# Arduino_Uno_Data_Logger_with_DHT.net
KiCad netlist of a schematic drawn in EAGLE
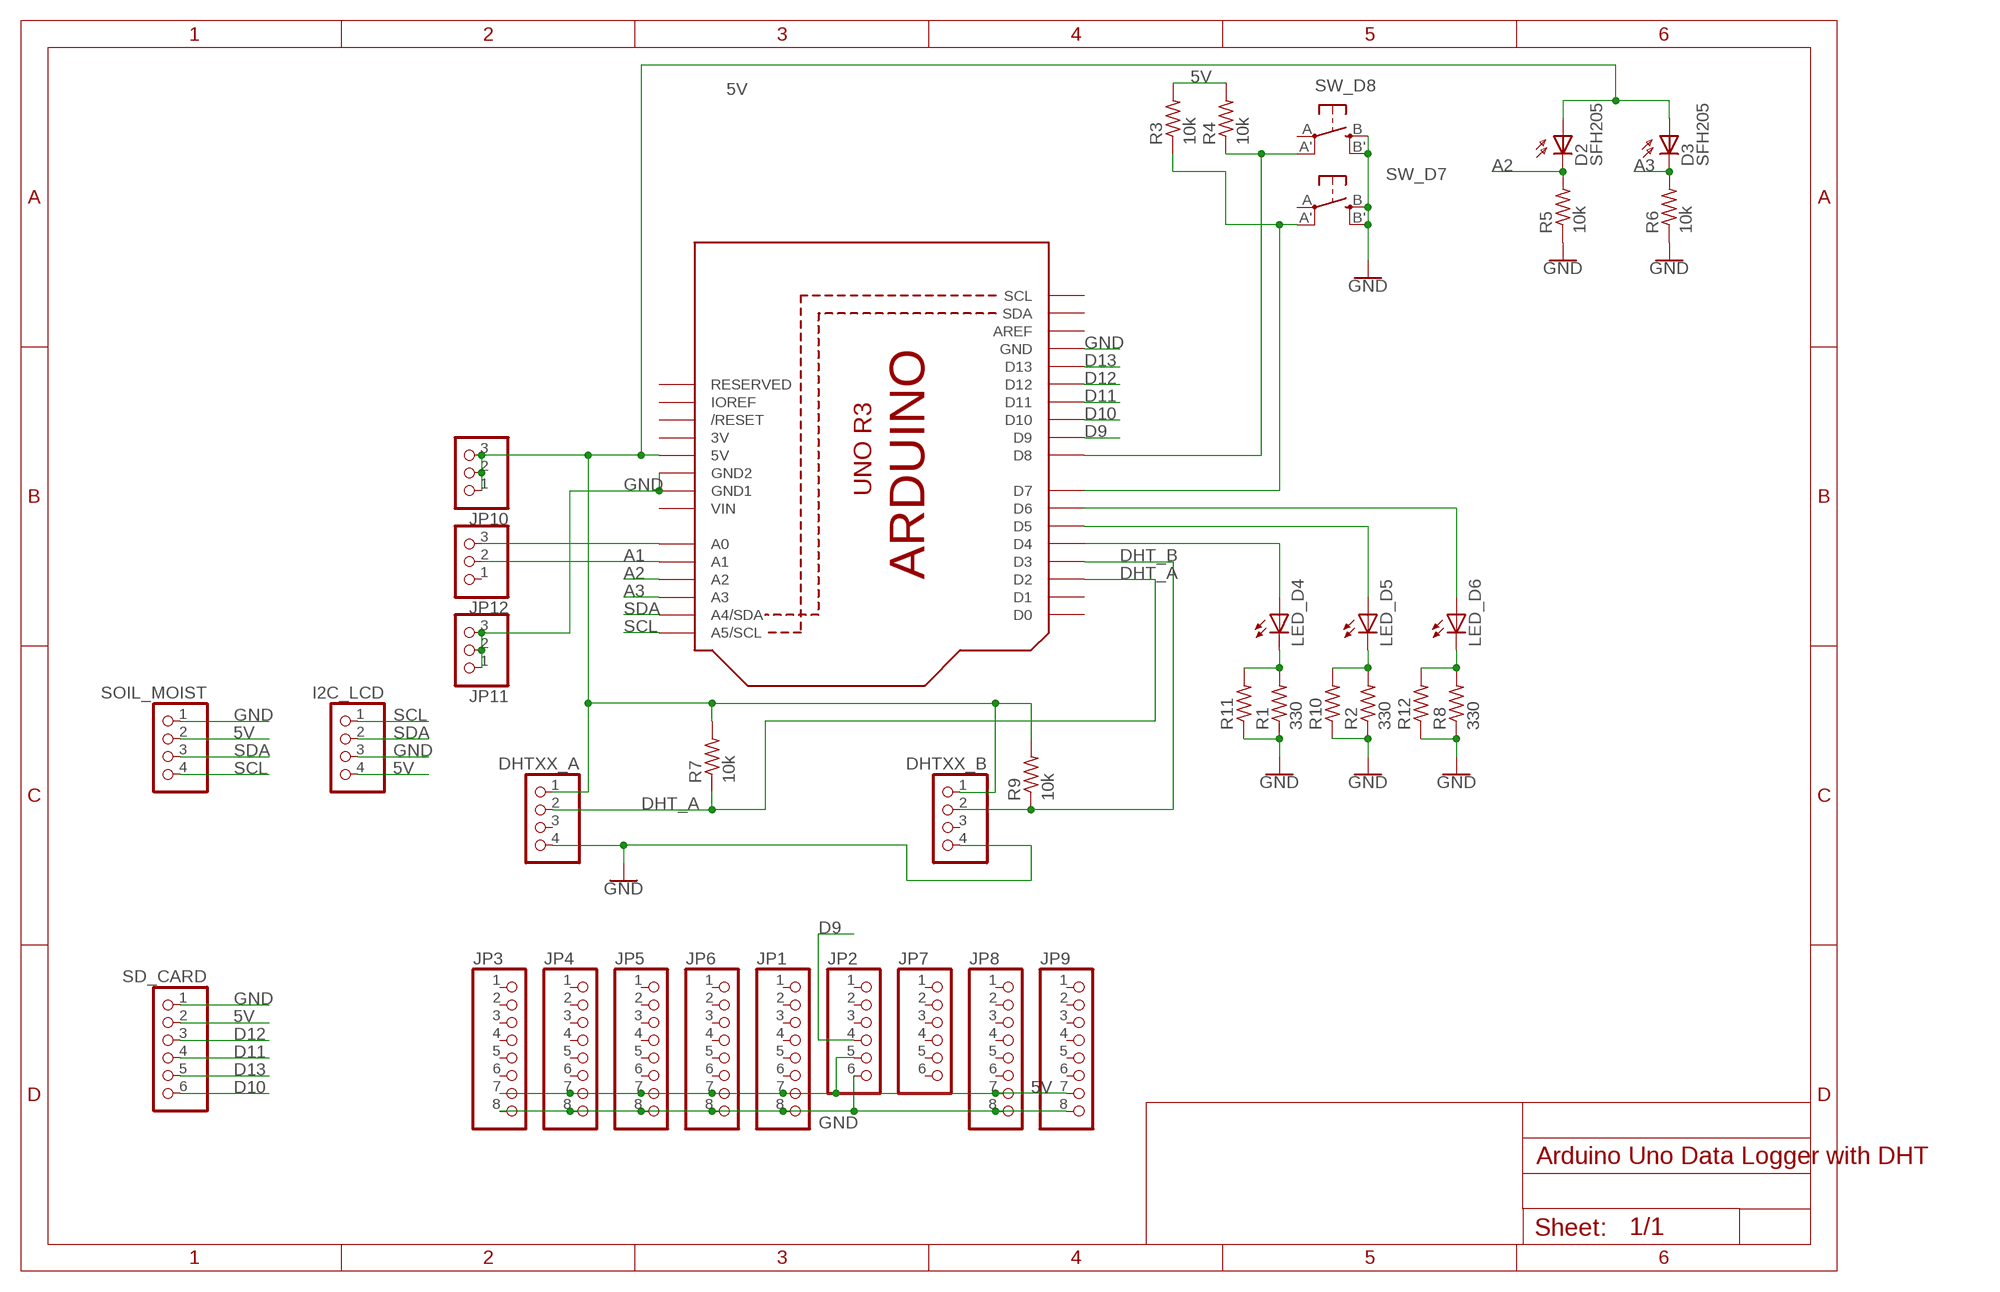
[diagram p0: schematic, sheet 1]

(export (version "E")
  (design (tool "Eeschema 10.0.6"))
  (components
    (comp (ref "D2")
      (value "SFH205")
      (footprint "eagle-import:SFH205")
      (libsource (lib "eagle-import") (part "SFH205"))
    )
    (comp (ref "D3")
      (value "SFH205")
      (footprint "eagle-import:SFH205")
      (libsource (lib "eagle-import") (part "SFH205"))
    )
    (comp (ref "DHTXX_A")
      (value "PINHD-1X4")
      (footprint "eagle-import:1X04")
      (libsource (lib "eagle-import") (part "PINHD-1X4"))
    )
    (comp (ref "DHTXX_B")
      (value "PINHD-1X4")
      (footprint "eagle-import:1X04")
      (libsource (lib "eagle-import") (part "PINHD-1X4"))
    )
    (comp (ref "I2C_LCD")
      (value "PINHD-1X4")
      (footprint "eagle-import:1X04")
      (libsource (lib "eagle-import") (part "PINHD-1X4"))
    )
    (comp (ref "JP1")
      (value "PINHD-1X8CLEANBIG")
      (footprint "eagle-import:1X08-CLEANBIG")
      (libsource (lib "eagle-import") (part "PINHD-1X8CLEANBIG"))
    )
    (comp (ref "JP2")
      (value "PINHD-1X6CB")
      (footprint "eagle-import:1X06-CLEANBIG")
      (libsource (lib "eagle-import") (part "PINHD-1X6CB"))
    )
    (comp (ref "JP3")
      (value "PINHD-1X8CLEANBIG")
      (footprint "eagle-import:1X08-CLEANBIG")
      (libsource (lib "eagle-import") (part "PINHD-1X8CLEANBIG"))
    )
    (comp (ref "JP4")
      (value "PINHD-1X8CLEANBIG")
      (footprint "eagle-import:1X08-CLEANBIG")
      (libsource (lib "eagle-import") (part "PINHD-1X8CLEANBIG"))
    )
    (comp (ref "JP5")
      (value "PINHD-1X8CLEANBIG")
      (footprint "eagle-import:1X08-CLEANBIG")
      (libsource (lib "eagle-import") (part "PINHD-1X8CLEANBIG"))
    )
    (comp (ref "JP6")
      (value "PINHD-1X8CLEANBIG")
      (footprint "eagle-import:1X08-CLEANBIG")
      (libsource (lib "eagle-import") (part "PINHD-1X8CLEANBIG"))
    )
    (comp (ref "JP7")
      (value "PINHD-1X6CB")
      (footprint "eagle-import:1X06-CLEANBIG")
      (libsource (lib "eagle-import") (part "PINHD-1X6CB"))
    )
    (comp (ref "JP8")
      (value "PINHD-1X8CLEANBIG")
      (footprint "eagle-import:1X08-CLEANBIG")
      (libsource (lib "eagle-import") (part "PINHD-1X8CLEANBIG"))
    )
    (comp (ref "JP9")
      (value "PINHD-1X8CLEANBIG")
      (footprint "eagle-import:1X08-CLEANBIG")
      (libsource (lib "eagle-import") (part "PINHD-1X8CLEANBIG"))
    )
    (comp (ref "JP10")
      (value "PINHD-1X3CB")
      (footprint "eagle-import:1X03-CLEANBIG")
      (libsource (lib "eagle-import") (part "PINHD-1X3CB"))
    )
    (comp (ref "JP11")
      (value "PINHD-1X3CB")
      (footprint "eagle-import:1X03-CLEANBIG")
      (libsource (lib "eagle-import") (part "PINHD-1X3CB"))
    )
    (comp (ref "JP12")
      (value "PINHD-1X3CB")
      (footprint "eagle-import:1X03-CLEANBIG")
      (libsource (lib "eagle-import") (part "PINHD-1X3CB"))
    )
    (comp (ref "LED_D4")
      (value "LED5MM")
      (footprint "eagle-import:LED5MM")
      (libsource (lib "eagle-import") (part "LED5MM"))
    )
    (comp (ref "LED_D5")
      (value "LED5MM")
      (footprint "eagle-import:LED5MM")
      (libsource (lib "eagle-import") (part "LED5MM"))
    )
    (comp (ref "LED_D6")
      (value "LED5MM")
      (footprint "eagle-import:LED5MM")
      (libsource (lib "eagle-import") (part "LED5MM"))
    )
    (comp (ref "R1")
      (value "330")
      (footprint "eagle-import:0207_10")
      (libsource (lib "eagle-import") (part "R-US_0207/10"))
    )
    (comp (ref "R2")
      (value "330")
      (footprint "eagle-import:0207_10")
      (libsource (lib "eagle-import") (part "R-US_0207/10"))
    )
    (comp (ref "R3")
      (value "10k")
      (footprint "eagle-import:0207_10")
      (libsource (lib "eagle-import") (part "R-US_0207/10"))
    )
    (comp (ref "R4")
      (value "10k")
      (footprint "eagle-import:0207_10")
      (libsource (lib "eagle-import") (part "R-US_0207/10"))
    )
    (comp (ref "R5")
      (value "10k")
      (footprint "eagle-import:0207_10")
      (libsource (lib "eagle-import") (part "R-US_0207/10"))
    )
    (comp (ref "R6")
      (value "10k")
      (footprint "eagle-import:0207_10")
      (libsource (lib "eagle-import") (part "R-US_0207/10"))
    )
    (comp (ref "R7")
      (value "10k")
      (footprint "eagle-import:0207_10")
      (libsource (lib "eagle-import") (part "R-US_0207/10"))
    )
    (comp (ref "R8")
      (value "330")
      (footprint "eagle-import:0207_10")
      (libsource (lib "eagle-import") (part "R-US_0207/10"))
    )
    (comp (ref "R9")
      (value "10k")
      (footprint "eagle-import:0207_10")
      (libsource (lib "eagle-import") (part "R-US_0207/10"))
    )
    (comp (ref "R10")
      (value "R-US_R2010")
      (footprint "eagle-import:R2010")
      (libsource (lib "eagle-import") (part "R-US_R2010"))
    )
    (comp (ref "R11")
      (value "R-US_R2010")
      (footprint "eagle-import:R2010")
      (libsource (lib "eagle-import") (part "R-US_R2010"))
    )
    (comp (ref "R12")
      (value "R-US_R2010")
      (footprint "eagle-import:R2010")
      (libsource (lib "eagle-import") (part "R-US_R2010"))
    )
    (comp (ref "SD_CARD")
      (value "PINHD-1X6")
      (footprint "eagle-import:1X06")
      (libsource (lib "eagle-import") (part "pinhead_PINHD-1X6"))
    )
    (comp (ref "SOIL_MOIST")
      (value "PINHD-1X4")
      (footprint "eagle-import:1X04")
      (libsource (lib "eagle-import") (part "PINHD-1X4"))
    )
    (comp (ref "SW_D7")
      (value "SPST_TACT-EVQQ2")
      (footprint "eagle-import:EVQ-Q2")
      (libsource (lib "eagle-import") (part "SPST_TACT-EVQQ2"))
    )
    (comp (ref "SW_D8")
      (value "SPST_TACT-EVQQ2")
      (footprint "eagle-import:EVQ-Q2")
      (libsource (lib "eagle-import") (part "SPST_TACT-EVQQ2"))
    )
    (comp (ref "U1")
      (value "ARDUINOR3-DIMENSION")
      (footprint "eagle-import:ARDUINOR3")
      (libsource (lib "eagle-import") (part "ARDUINOR3-DIMENSION"))
    )
  )
  (nets
    (net (code "1") (name "/3V") (class "Default")
      (node (ref "U1") (pin "3V") (pinfunction "3V_3V") (pintype "power_in"))
    )
    (net (code "2") (name "/5V") (class "Default")
      (node (ref "D2") (pin "A") (pinfunction "A_A") (pintype "passive"))
      (node (ref "D3") (pin "A") (pinfunction "A_A") (pintype "passive"))
      (node (ref "DHTXX_A") (pin "1") (pinfunction "1_1") (pintype "passive"))
      (node (ref "DHTXX_B") (pin "1") (pinfunction "1_1") (pintype "passive"))
      (node (ref "I2C_LCD") (pin "4") (pinfunction "4_4") (pintype "passive"))
      (node (ref "JP1") (pin "7") (pinfunction "7_7") (pintype "passive"))
      (node (ref "JP10") (pin "1") (pinfunction "1_1") (pintype "passive"))
      (node (ref "JP10") (pin "2") (pinfunction "2_2") (pintype "passive"))
      (node (ref "JP10") (pin "3") (pinfunction "3_3") (pintype "passive"))
      (node (ref "JP2") (pin "5") (pinfunction "5_5") (pintype "passive"))
      (node (ref "JP3") (pin "7") (pinfunction "7_7") (pintype "passive"))
      (node (ref "JP4") (pin "7") (pinfunction "7_7") (pintype "passive"))
      (node (ref "JP5") (pin "7") (pinfunction "7_7") (pintype "passive"))
      (node (ref "JP6") (pin "7") (pinfunction "7_7") (pintype "passive"))
      (node (ref "JP8") (pin "7") (pinfunction "7_7") (pintype "passive"))
      (node (ref "JP9") (pin "7") (pinfunction "7_7") (pintype "passive"))
      (node (ref "R3") (pin "2") (pinfunction "2_2") (pintype "passive"))
      (node (ref "R4") (pin "2") (pinfunction "2_2") (pintype "passive"))
      (node (ref "R7") (pin "2") (pinfunction "2_2") (pintype "passive"))
      (node (ref "R9") (pin "2") (pinfunction "2_2") (pintype "passive"))
      (node (ref "SD_CARD") (pin "2") (pinfunction "2_2") (pintype "passive"))
      (node (ref "SOIL_MOIST") (pin "2") (pinfunction "2_2") (pintype "passive"))
      (node (ref "U1") (pin "5V") (pinfunction "5V_5V") (pintype "power_in"))
    )
    (net (code "3") (name "/A1") (class "Default")
      (node (ref "JP12") (pin "2") (pinfunction "2_2") (pintype "passive"))
      (node (ref "U1") (pin "A1") (pinfunction "A1_A1") (pintype "bidirectional"))
    )
    (net (code "4") (name "/A2") (class "Default")
      (node (ref "D2") (pin "K") (pinfunction "C_K") (pintype "passive"))
      (node (ref "R5") (pin "2") (pinfunction "2_2") (pintype "passive"))
      (node (ref "U1") (pin "A2") (pinfunction "A2_A2") (pintype "bidirectional"))
    )
    (net (code "5") (name "/A3") (class "Default")
      (node (ref "D3") (pin "K") (pinfunction "C_K") (pintype "passive"))
      (node (ref "R6") (pin "2") (pinfunction "2_2") (pintype "passive"))
      (node (ref "U1") (pin "A3") (pinfunction "A3_A3") (pintype "bidirectional"))
    )
    (net (code "6") (name "/D9") (class "Default")
      (node (ref "JP2") (pin "4") (pinfunction "4_4") (pintype "passive"))
      (node (ref "U1") (pin "D9") (pinfunction "D9_D9") (pintype "bidirectional"))
    )
    (net (code "7") (name "/D10") (class "Default")
      (node (ref "SD_CARD") (pin "6") (pinfunction "6_6") (pintype "passive"))
      (node (ref "U1") (pin "D10") (pinfunction "D10_D10") (pintype "bidirectional"))
    )
    (net (code "8") (name "/D11") (class "Default")
      (node (ref "SD_CARD") (pin "4") (pinfunction "4_4") (pintype "passive"))
      (node (ref "U1") (pin "D11") (pinfunction "D11_D11") (pintype "bidirectional"))
    )
    (net (code "9") (name "/D12") (class "Default")
      (node (ref "SD_CARD") (pin "3") (pinfunction "3_3") (pintype "passive"))
      (node (ref "U1") (pin "D12") (pinfunction "D12_D12") (pintype "bidirectional"))
    )
    (net (code "10") (name "/D13") (class "Default")
      (node (ref "SD_CARD") (pin "5") (pinfunction "5_5") (pintype "passive"))
      (node (ref "U1") (pin "D13") (pinfunction "D13_D13") (pintype "bidirectional"))
    )
    (net (code "11") (name "/DHT_A") (class "Default")
      (node (ref "DHTXX_A") (pin "2") (pinfunction "2_2") (pintype "passive"))
      (node (ref "R7") (pin "1") (pinfunction "1_1") (pintype "passive"))
      (node (ref "U1") (pin "D2") (pinfunction "D2_D2") (pintype "bidirectional"))
    )
    (net (code "12") (name "/DHT_B") (class "Default")
      (node (ref "DHTXX_B") (pin "2") (pinfunction "2_2") (pintype "passive"))
      (node (ref "R9") (pin "1") (pinfunction "1_1") (pintype "passive"))
      (node (ref "U1") (pin "D3") (pinfunction "D3_D3") (pintype "bidirectional"))
    )
    (net (code "13") (name "/SCL") (class "Default")
      (node (ref "I2C_LCD") (pin "1") (pinfunction "1_1") (pintype "passive"))
      (node (ref "SOIL_MOIST") (pin "4") (pinfunction "4_4") (pintype "passive"))
      (node (ref "U1") (pin "A5") (pinfunction "A5/SCL_A5") (pintype "bidirectional"))
    )
    (net (code "14") (name "/SDA") (class "Default")
      (node (ref "I2C_LCD") (pin "2") (pinfunction "2_2") (pintype "passive"))
      (node (ref "SOIL_MOIST") (pin "3") (pinfunction "3_3") (pintype "passive"))
      (node (ref "U1") (pin "A4") (pinfunction "A4/SDA_A4") (pintype "bidirectional"))
    )
    (net (code "15") (name "/VIN") (class "Default")
      (node (ref "U1") (pin "VIN") (pinfunction "VIN_VIN") (pintype "power_in"))
    )
    (net (code "16") (name "GND") (class "Default")
      (node (ref "DHTXX_A") (pin "4") (pinfunction "4_4") (pintype "passive"))
      (node (ref "DHTXX_B") (pin "4") (pinfunction "4_4") (pintype "passive"))
      (node (ref "I2C_LCD") (pin "3") (pinfunction "3_3") (pintype "passive"))
      (node (ref "JP1") (pin "8") (pinfunction "8_8") (pintype "passive"))
      (node (ref "JP11") (pin "1") (pinfunction "1_1") (pintype "passive"))
      (node (ref "JP11") (pin "2") (pinfunction "2_2") (pintype "passive"))
      (node (ref "JP11") (pin "3") (pinfunction "3_3") (pintype "passive"))
      (node (ref "JP2") (pin "6") (pinfunction "6_6") (pintype "passive"))
      (node (ref "JP3") (pin "8") (pinfunction "8_8") (pintype "passive"))
      (node (ref "JP4") (pin "8") (pinfunction "8_8") (pintype "passive"))
      (node (ref "JP5") (pin "8") (pinfunction "8_8") (pintype "passive"))
      (node (ref "JP6") (pin "8") (pinfunction "8_8") (pintype "passive"))
      (node (ref "JP8") (pin "8") (pinfunction "8_8") (pintype "passive"))
      (node (ref "JP9") (pin "8") (pinfunction "8_8") (pintype "passive"))
      (node (ref "R1") (pin "1") (pinfunction "1_1") (pintype "passive"))
      (node (ref "R10") (pin "1") (pinfunction "1_1") (pintype "passive"))
      (node (ref "R11") (pin "1") (pinfunction "1_1") (pintype "passive"))
      (node (ref "R12") (pin "1") (pinfunction "1_1") (pintype "passive"))
      (node (ref "R2") (pin "1") (pinfunction "1_1") (pintype "passive"))
      (node (ref "R5") (pin "1") (pinfunction "1_1") (pintype "passive"))
      (node (ref "R6") (pin "1") (pinfunction "1_1") (pintype "passive"))
      (node (ref "R8") (pin "1") (pinfunction "1_1") (pintype "passive"))
      (node (ref "SD_CARD") (pin "1") (pinfunction "1_1") (pintype "passive"))
      (node (ref "SOIL_MOIST") (pin "1") (pinfunction "1_1") (pintype "passive"))
      (node (ref "SW_D7") (pin "B") (pinfunction "S_B") (pintype "passive"))
      (node (ref "SW_D7") (pin "B'") (pinfunction "S1_B'") (pintype "passive"))
      (node (ref "SW_D8") (pin "B") (pinfunction "S_B") (pintype "passive"))
      (node (ref "SW_D8") (pin "B'") (pinfunction "S1_B'") (pintype "passive"))
      (node (ref "U1") (pin "GND") (pinfunction "GND_GND") (pintype "power_in"))
      (node (ref "U1") (pin "GND1") (pinfunction "GND1_GND1") (pintype "power_in"))
      (node (ref "U1") (pin "GND2") (pinfunction "GND2_GND2") (pintype "power_in"))
    )
    (net (code "17") (name "Net-(JP12-Pad3)") (class "Default")
      (node (ref "JP12") (pin "3") (pinfunction "3_3") (pintype "passive"))
      (node (ref "U1") (pin "A0") (pinfunction "A0_A0") (pintype "bidirectional"))
    )
    (net (code "18") (name "Net-(LED_D4-C)") (class "Default")
      (node (ref "LED_D4") (pin "K") (pinfunction "C_K") (pintype "passive"))
      (node (ref "R1") (pin "2") (pinfunction "2_2") (pintype "passive"))
      (node (ref "R11") (pin "2") (pinfunction "2_2") (pintype "passive"))
    )
    (net (code "19") (name "Net-(LED_D4-PadA)") (class "Default")
      (node (ref "LED_D4") (pin "A") (pinfunction "A_A") (pintype "passive"))
      (node (ref "U1") (pin "D4") (pinfunction "D4_D4") (pintype "bidirectional"))
    )
    (net (code "20") (name "Net-(LED_D5-C)") (class "Default")
      (node (ref "LED_D5") (pin "K") (pinfunction "C_K") (pintype "passive"))
      (node (ref "R10") (pin "2") (pinfunction "2_2") (pintype "passive"))
      (node (ref "R2") (pin "2") (pinfunction "2_2") (pintype "passive"))
    )
    (net (code "21") (name "Net-(LED_D5-PadA)") (class "Default")
      (node (ref "LED_D5") (pin "A") (pinfunction "A_A") (pintype "passive"))
      (node (ref "U1") (pin "D5") (pinfunction "D5_D5") (pintype "bidirectional"))
    )
    (net (code "22") (name "Net-(LED_D6-C)") (class "Default")
      (node (ref "LED_D6") (pin "K") (pinfunction "C_K") (pintype "passive"))
      (node (ref "R12") (pin "2") (pinfunction "2_2") (pintype "passive"))
      (node (ref "R8") (pin "2") (pinfunction "2_2") (pintype "passive"))
    )
    (net (code "23") (name "Net-(LED_D6-PadA)") (class "Default")
      (node (ref "LED_D6") (pin "A") (pinfunction "A_A") (pintype "passive"))
      (node (ref "U1") (pin "D6") (pinfunction "D6_D6") (pintype "bidirectional"))
    )
    (net (code "24") (name "Net-(SW_D7-P1)") (class "Default")
      (node (ref "R3") (pin "1") (pinfunction "1_1") (pintype "passive"))
      (node (ref "SW_D7") (pin "A'") (pinfunction "P1_A'") (pintype "passive"))
      (node (ref "U1") (pin "D7") (pinfunction "D7_D7") (pintype "bidirectional"))
    )
    (net (code "25") (name "Net-(SW_D8-P1)") (class "Default")
      (node (ref "R4") (pin "1") (pinfunction "1_1") (pintype "passive"))
      (node (ref "SW_D8") (pin "A'") (pinfunction "P1_A'") (pintype "passive"))
      (node (ref "U1") (pin "D8") (pinfunction "D8_D8") (pintype "bidirectional"))
    )
    (net (code "26") (name "unconnected-(DHTXX_A-Pad3)") (class "Default")
      (node (ref "DHTXX_A") (pin "3") (pinfunction "3_3") (pintype "passive"))
    )
    (net (code "27") (name "unconnected-(DHTXX_B-Pad3)") (class "Default")
      (node (ref "DHTXX_B") (pin "3") (pinfunction "3_3") (pintype "passive"))
    )
    (net (code "28") (name "unconnected-(JP1-Pad1)") (class "Default")
      (node (ref "JP1") (pin "1") (pinfunction "1_1") (pintype "passive"))
    )
    (net (code "29") (name "unconnected-(JP1-Pad2)") (class "Default")
      (node (ref "JP1") (pin "2") (pinfunction "2_2") (pintype "passive"))
    )
    (net (code "30") (name "unconnected-(JP1-Pad3)") (class "Default")
      (node (ref "JP1") (pin "3") (pinfunction "3_3") (pintype "passive"))
    )
    (net (code "31") (name "unconnected-(JP1-Pad4)") (class "Default")
      (node (ref "JP1") (pin "4") (pinfunction "4_4") (pintype "passive"))
    )
    (net (code "32") (name "unconnected-(JP1-Pad5)") (class "Default")
      (node (ref "JP1") (pin "5") (pinfunction "5_5") (pintype "passive"))
    )
    (net (code "33") (name "unconnected-(JP1-Pad6)") (class "Default")
      (node (ref "JP1") (pin "6") (pinfunction "6_6") (pintype "passive"))
    )
    (net (code "34") (name "unconnected-(JP2-Pad1)") (class "Default")
      (node (ref "JP2") (pin "1") (pinfunction "1_1") (pintype "passive"))
    )
    (net (code "35") (name "unconnected-(JP2-Pad2)") (class "Default")
      (node (ref "JP2") (pin "2") (pinfunction "2_2") (pintype "passive"))
    )
    (net (code "36") (name "unconnected-(JP2-Pad3)") (class "Default")
      (node (ref "JP2") (pin "3") (pinfunction "3_3") (pintype "passive"))
    )
    (net (code "37") (name "unconnected-(JP3-Pad1)") (class "Default")
      (node (ref "JP3") (pin "1") (pinfunction "1_1") (pintype "passive"))
    )
    (net (code "38") (name "unconnected-(JP3-Pad2)") (class "Default")
      (node (ref "JP3") (pin "2") (pinfunction "2_2") (pintype "passive"))
    )
    (net (code "39") (name "unconnected-(JP3-Pad3)") (class "Default")
      (node (ref "JP3") (pin "3") (pinfunction "3_3") (pintype "passive"))
    )
    (net (code "40") (name "unconnected-(JP3-Pad4)") (class "Default")
      (node (ref "JP3") (pin "4") (pinfunction "4_4") (pintype "passive"))
    )
    (net (code "41") (name "unconnected-(JP3-Pad5)") (class "Default")
      (node (ref "JP3") (pin "5") (pinfunction "5_5") (pintype "passive"))
    )
    (net (code "42") (name "unconnected-(JP3-Pad6)") (class "Default")
      (node (ref "JP3") (pin "6") (pinfunction "6_6") (pintype "passive"))
    )
    (net (code "43") (name "unconnected-(JP4-Pad1)") (class "Default")
      (node (ref "JP4") (pin "1") (pinfunction "1_1") (pintype "passive"))
    )
    (net (code "44") (name "unconnected-(JP4-Pad2)") (class "Default")
      (node (ref "JP4") (pin "2") (pinfunction "2_2") (pintype "passive"))
    )
    (net (code "45") (name "unconnected-(JP4-Pad3)") (class "Default")
      (node (ref "JP4") (pin "3") (pinfunction "3_3") (pintype "passive"))
    )
    (net (code "46") (name "unconnected-(JP4-Pad4)") (class "Default")
      (node (ref "JP4") (pin "4") (pinfunction "4_4") (pintype "passive"))
    )
    (net (code "47") (name "unconnected-(JP4-Pad5)") (class "Default")
      (node (ref "JP4") (pin "5") (pinfunction "5_5") (pintype "passive"))
    )
    (net (code "48") (name "unconnected-(JP4-Pad6)") (class "Default")
      (node (ref "JP4") (pin "6") (pinfunction "6_6") (pintype "passive"))
    )
    (net (code "49") (name "unconnected-(JP5-Pad1)") (class "Default")
      (node (ref "JP5") (pin "1") (pinfunction "1_1") (pintype "passive"))
    )
    (net (code "50") (name "unconnected-(JP5-Pad2)") (class "Default")
      (node (ref "JP5") (pin "2") (pinfunction "2_2") (pintype "passive"))
    )
    (net (code "51") (name "unconnected-(JP5-Pad3)") (class "Default")
      (node (ref "JP5") (pin "3") (pinfunction "3_3") (pintype "passive"))
    )
    (net (code "52") (name "unconnected-(JP5-Pad4)") (class "Default")
      (node (ref "JP5") (pin "4") (pinfunction "4_4") (pintype "passive"))
    )
    (net (code "53") (name "unconnected-(JP5-Pad5)") (class "Default")
      (node (ref "JP5") (pin "5") (pinfunction "5_5") (pintype "passive"))
    )
    (net (code "54") (name "unconnected-(JP5-Pad6)") (class "Default")
      (node (ref "JP5") (pin "6") (pinfunction "6_6") (pintype "passive"))
    )
    (net (code "55") (name "unconnected-(JP6-Pad1)") (class "Default")
      (node (ref "JP6") (pin "1") (pinfunction "1_1") (pintype "passive"))
    )
    (net (code "56") (name "unconnected-(JP6-Pad2)") (class "Default")
      (node (ref "JP6") (pin "2") (pinfunction "2_2") (pintype "passive"))
    )
    (net (code "57") (name "unconnected-(JP6-Pad3)") (class "Default")
      (node (ref "JP6") (pin "3") (pinfunction "3_3") (pintype "passive"))
    )
    (net (code "58") (name "unconnected-(JP6-Pad4)") (class "Default")
      (node (ref "JP6") (pin "4") (pinfunction "4_4") (pintype "passive"))
    )
    (net (code "59") (name "unconnected-(JP6-Pad5)") (class "Default")
      (node (ref "JP6") (pin "5") (pinfunction "5_5") (pintype "passive"))
    )
    (net (code "60") (name "unconnected-(JP6-Pad6)") (class "Default")
      (node (ref "JP6") (pin "6") (pinfunction "6_6") (pintype "passive"))
    )
    (net (code "61") (name "unconnected-(JP7-Pad1)") (class "Default")
      (node (ref "JP7") (pin "1") (pinfunction "1_1") (pintype "passive"))
    )
    (net (code "62") (name "unconnected-(JP7-Pad2)") (class "Default")
      (node (ref "JP7") (pin "2") (pinfunction "2_2") (pintype "passive"))
    )
    (net (code "63") (name "unconnected-(JP7-Pad3)") (class "Default")
      (node (ref "JP7") (pin "3") (pinfunction "3_3") (pintype "passive"))
    )
    (net (code "64") (name "unconnected-(JP7-Pad4)") (class "Default")
      (node (ref "JP7") (pin "4") (pinfunction "4_4") (pintype "passive"))
    )
    (net (code "65") (name "unconnected-(JP7-Pad5)") (class "Default")
      (node (ref "JP7") (pin "5") (pinfunction "5_5") (pintype "passive"))
    )
    (net (code "66") (name "unconnected-(JP7-Pad6)") (class "Default")
      (node (ref "JP7") (pin "6") (pinfunction "6_6") (pintype "passive"))
    )
    (net (code "67") (name "unconnected-(JP8-Pad1)") (class "Default")
      (node (ref "JP8") (pin "1") (pinfunction "1_1") (pintype "passive"))
    )
    (net (code "68") (name "unconnected-(JP8-Pad2)") (class "Default")
      (node (ref "JP8") (pin "2") (pinfunction "2_2") (pintype "passive"))
    )
    (net (code "69") (name "unconnected-(JP8-Pad3)") (class "Default")
      (node (ref "JP8") (pin "3") (pinfunction "3_3") (pintype "passive"))
    )
    (net (code "70") (name "unconnected-(JP8-Pad4)") (class "Default")
      (node (ref "JP8") (pin "4") (pinfunction "4_4") (pintype "passive"))
    )
    (net (code "71") (name "unconnected-(JP8-Pad5)") (class "Default")
      (node (ref "JP8") (pin "5") (pinfunction "5_5") (pintype "passive"))
    )
    (net (code "72") (name "unconnected-(JP8-Pad6)") (class "Default")
      (node (ref "JP8") (pin "6") (pinfunction "6_6") (pintype "passive"))
    )
    (net (code "73") (name "unconnected-(JP9-Pad1)") (class "Default")
      (node (ref "JP9") (pin "1") (pinfunction "1_1") (pintype "passive"))
    )
    (net (code "74") (name "unconnected-(JP9-Pad2)") (class "Default")
      (node (ref "JP9") (pin "2") (pinfunction "2_2") (pintype "passive"))
    )
    (net (code "75") (name "unconnected-(JP9-Pad3)") (class "Default")
      (node (ref "JP9") (pin "3") (pinfunction "3_3") (pintype "passive"))
    )
    (net (code "76") (name "unconnected-(JP9-Pad4)") (class "Default")
      (node (ref "JP9") (pin "4") (pinfunction "4_4") (pintype "passive"))
    )
    (net (code "77") (name "unconnected-(JP9-Pad5)") (class "Default")
      (node (ref "JP9") (pin "5") (pinfunction "5_5") (pintype "passive"))
    )
    (net (code "78") (name "unconnected-(JP9-Pad6)") (class "Default")
      (node (ref "JP9") (pin "6") (pinfunction "6_6") (pintype "passive"))
    )
    (net (code "79") (name "unconnected-(JP12-Pad1)") (class "Default")
      (node (ref "JP12") (pin "1") (pinfunction "1_1") (pintype "passive"))
    )
    (net (code "80") (name "unconnected-(SW_D7-P-PadA)") (class "Default")
      (node (ref "SW_D7") (pin "A") (pinfunction "P_A") (pintype "passive"))
    )
    (net (code "81") (name "unconnected-(SW_D8-P-PadA)") (class "Default")
      (node (ref "SW_D8") (pin "A") (pinfunction "P_A") (pintype "passive"))
    )
    (net (code "82") (name "unconnected-(U1-PadAREF)") (class "Default")
      (node (ref "U1") (pin "AREF") (pinfunction "AREF_AREF") (pintype "bidirectional"))
    )
    (net (code "83") (name "unconnected-(U1-PadD0)") (class "Default")
      (node (ref "U1") (pin "D0") (pinfunction "D0_D0") (pintype "bidirectional"))
    )
    (net (code "84") (name "unconnected-(U1-PadD1)") (class "Default")
      (node (ref "U1") (pin "D1") (pinfunction "D1_D1") (pintype "bidirectional"))
    )
    (net (code "85") (name "unconnected-(U1-PadIOREF)") (class "Default")
      (node (ref "U1") (pin "IOREF") (pinfunction "IOREF_IOREF") (pintype "output"))
    )
    (net (code "86") (name "unconnected-(U1-PadRESERVED)") (class "Default")
      (node (ref "U1") (pin "RESERVED") (pinfunction "RESERVED_RESERVED") (pintype "no_connect"))
    )
    (net (code "87") (name "unconnected-(U1-PadSCL)") (class "Default")
      (node (ref "U1") (pin "SCL") (pinfunction "SCL_SCL") (pintype "bidirectional"))
    )
    (net (code "88") (name "unconnected-(U1-PadSDA)") (class "Default")
      (node (ref "U1") (pin "SDA") (pinfunction "SDA_SDA") (pintype "bidirectional"))
    )
    (net (code "89") (name "unconnected-(U1-{slash}RESET-PadRESET)") (class "Default")
      (node (ref "U1") (pin "RESET") (pinfunction "/RESET_RESET") (pintype "bidirectional"))
    )
  )
)
